# PowerSupply_12V_v1.net
KiCad netlist of a schematic drawn in EAGLE
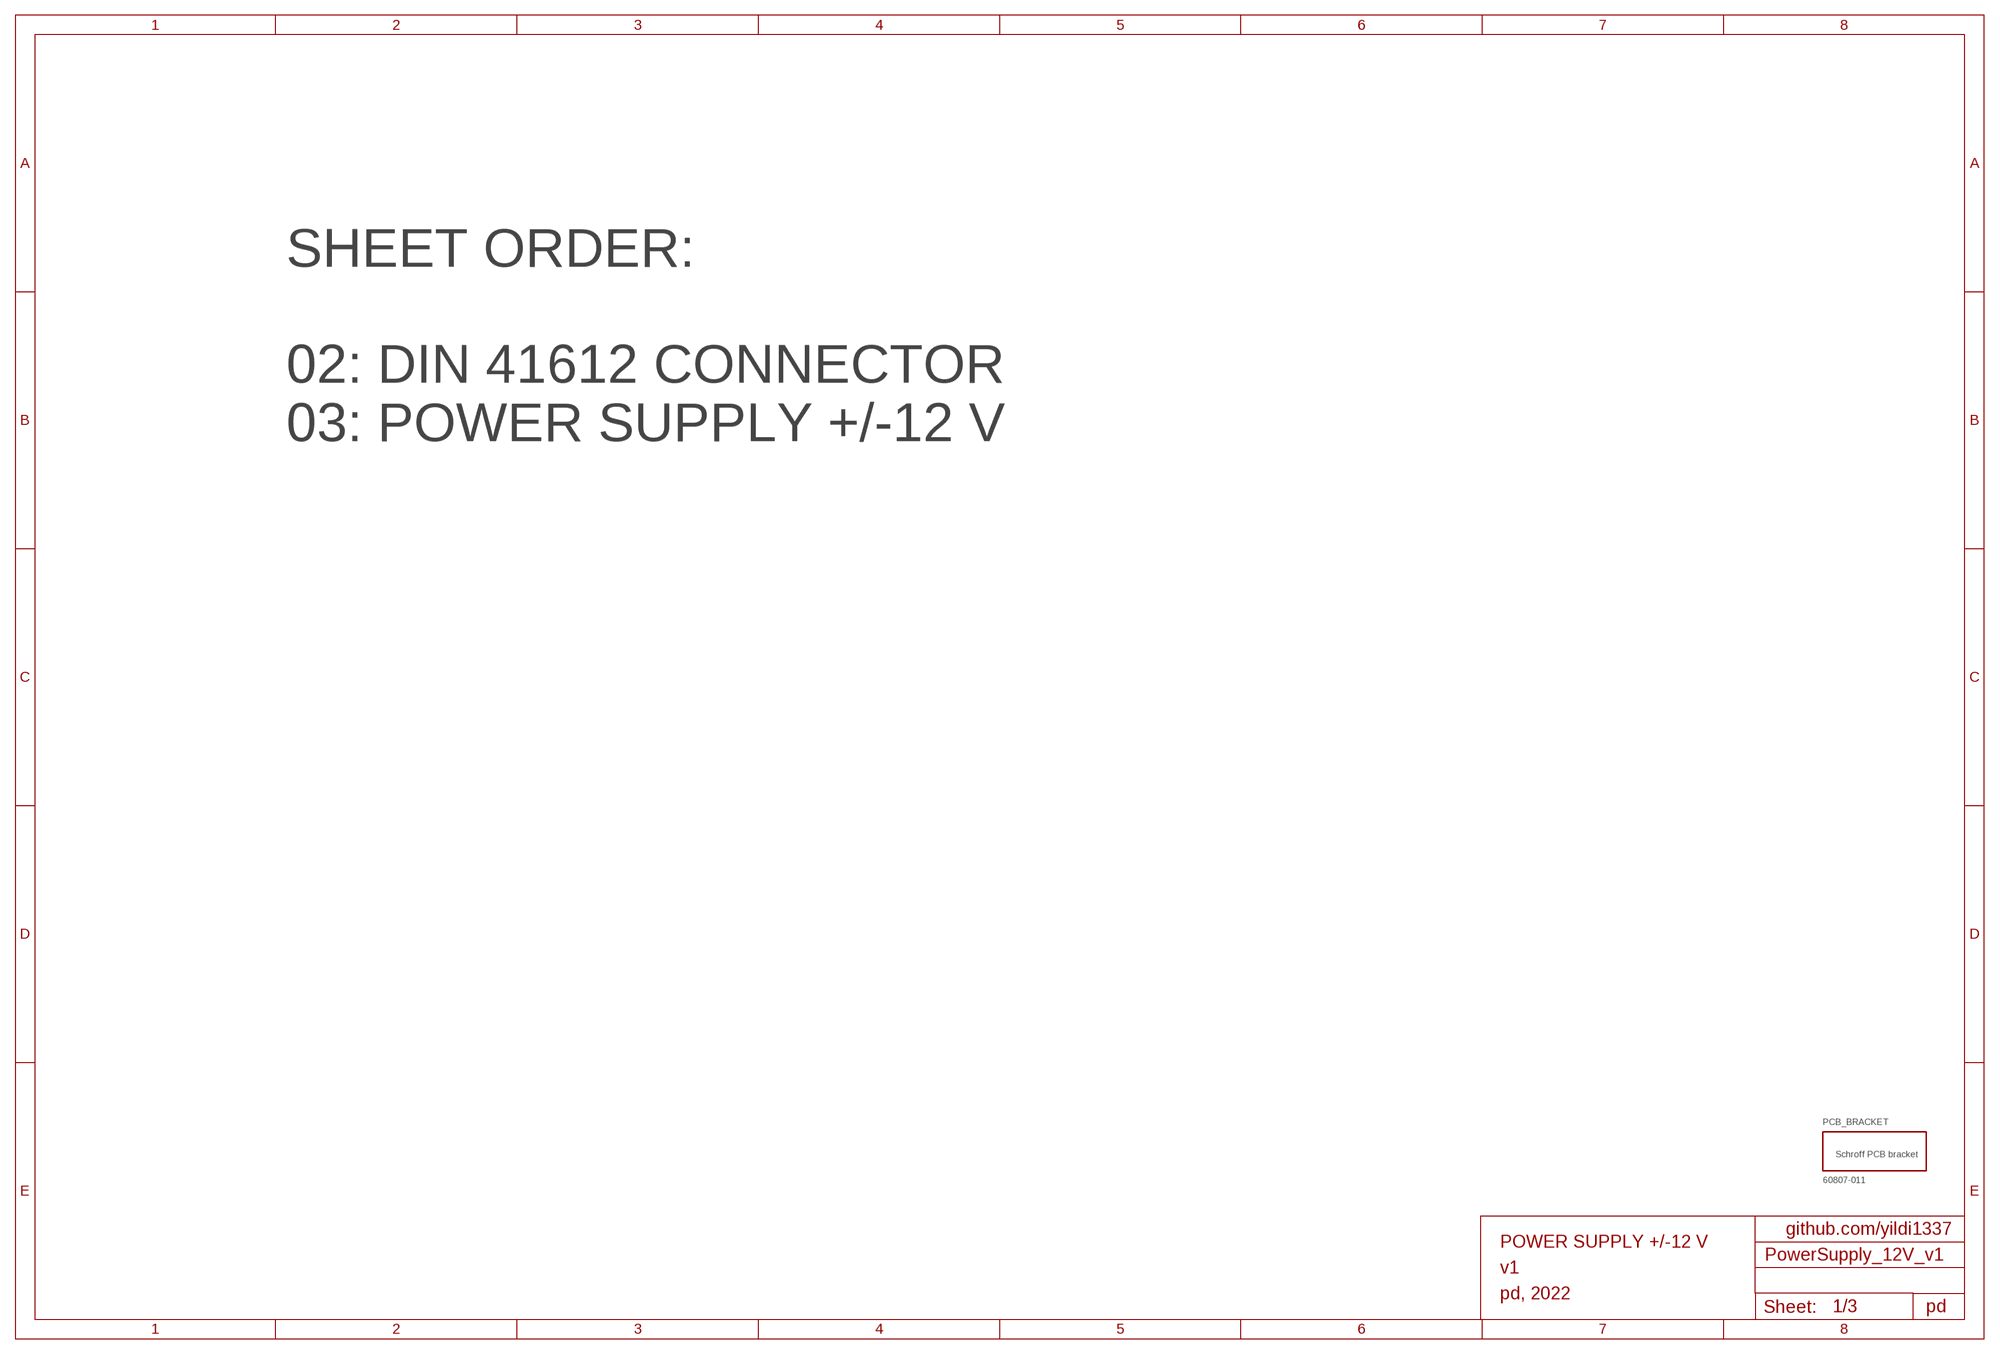
[diagram p0: schematic, sheet 1]
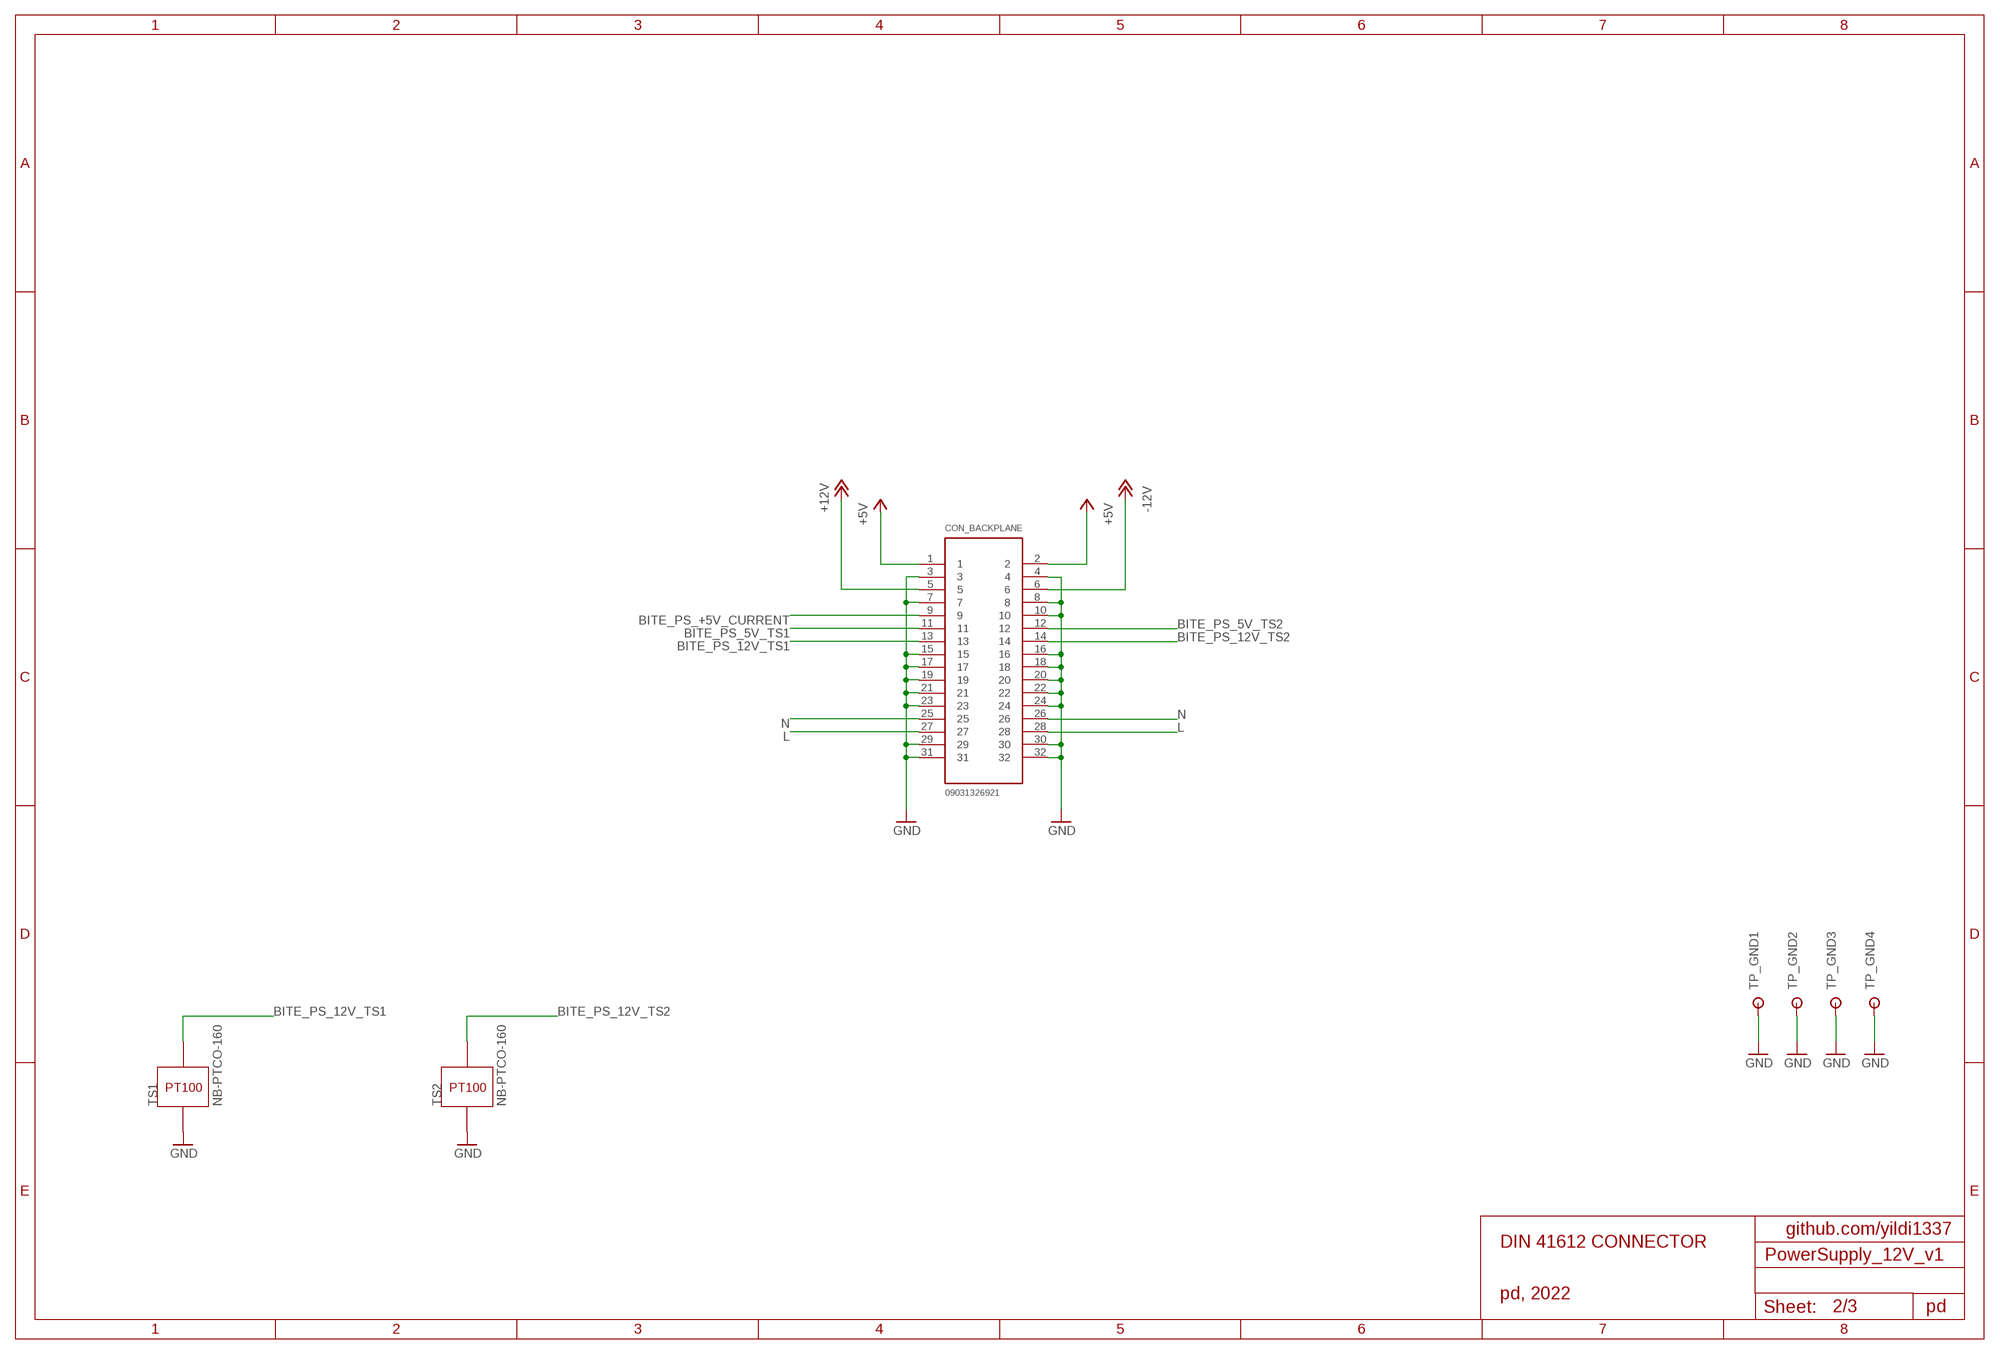
[diagram p1: schematic, sheet 2]
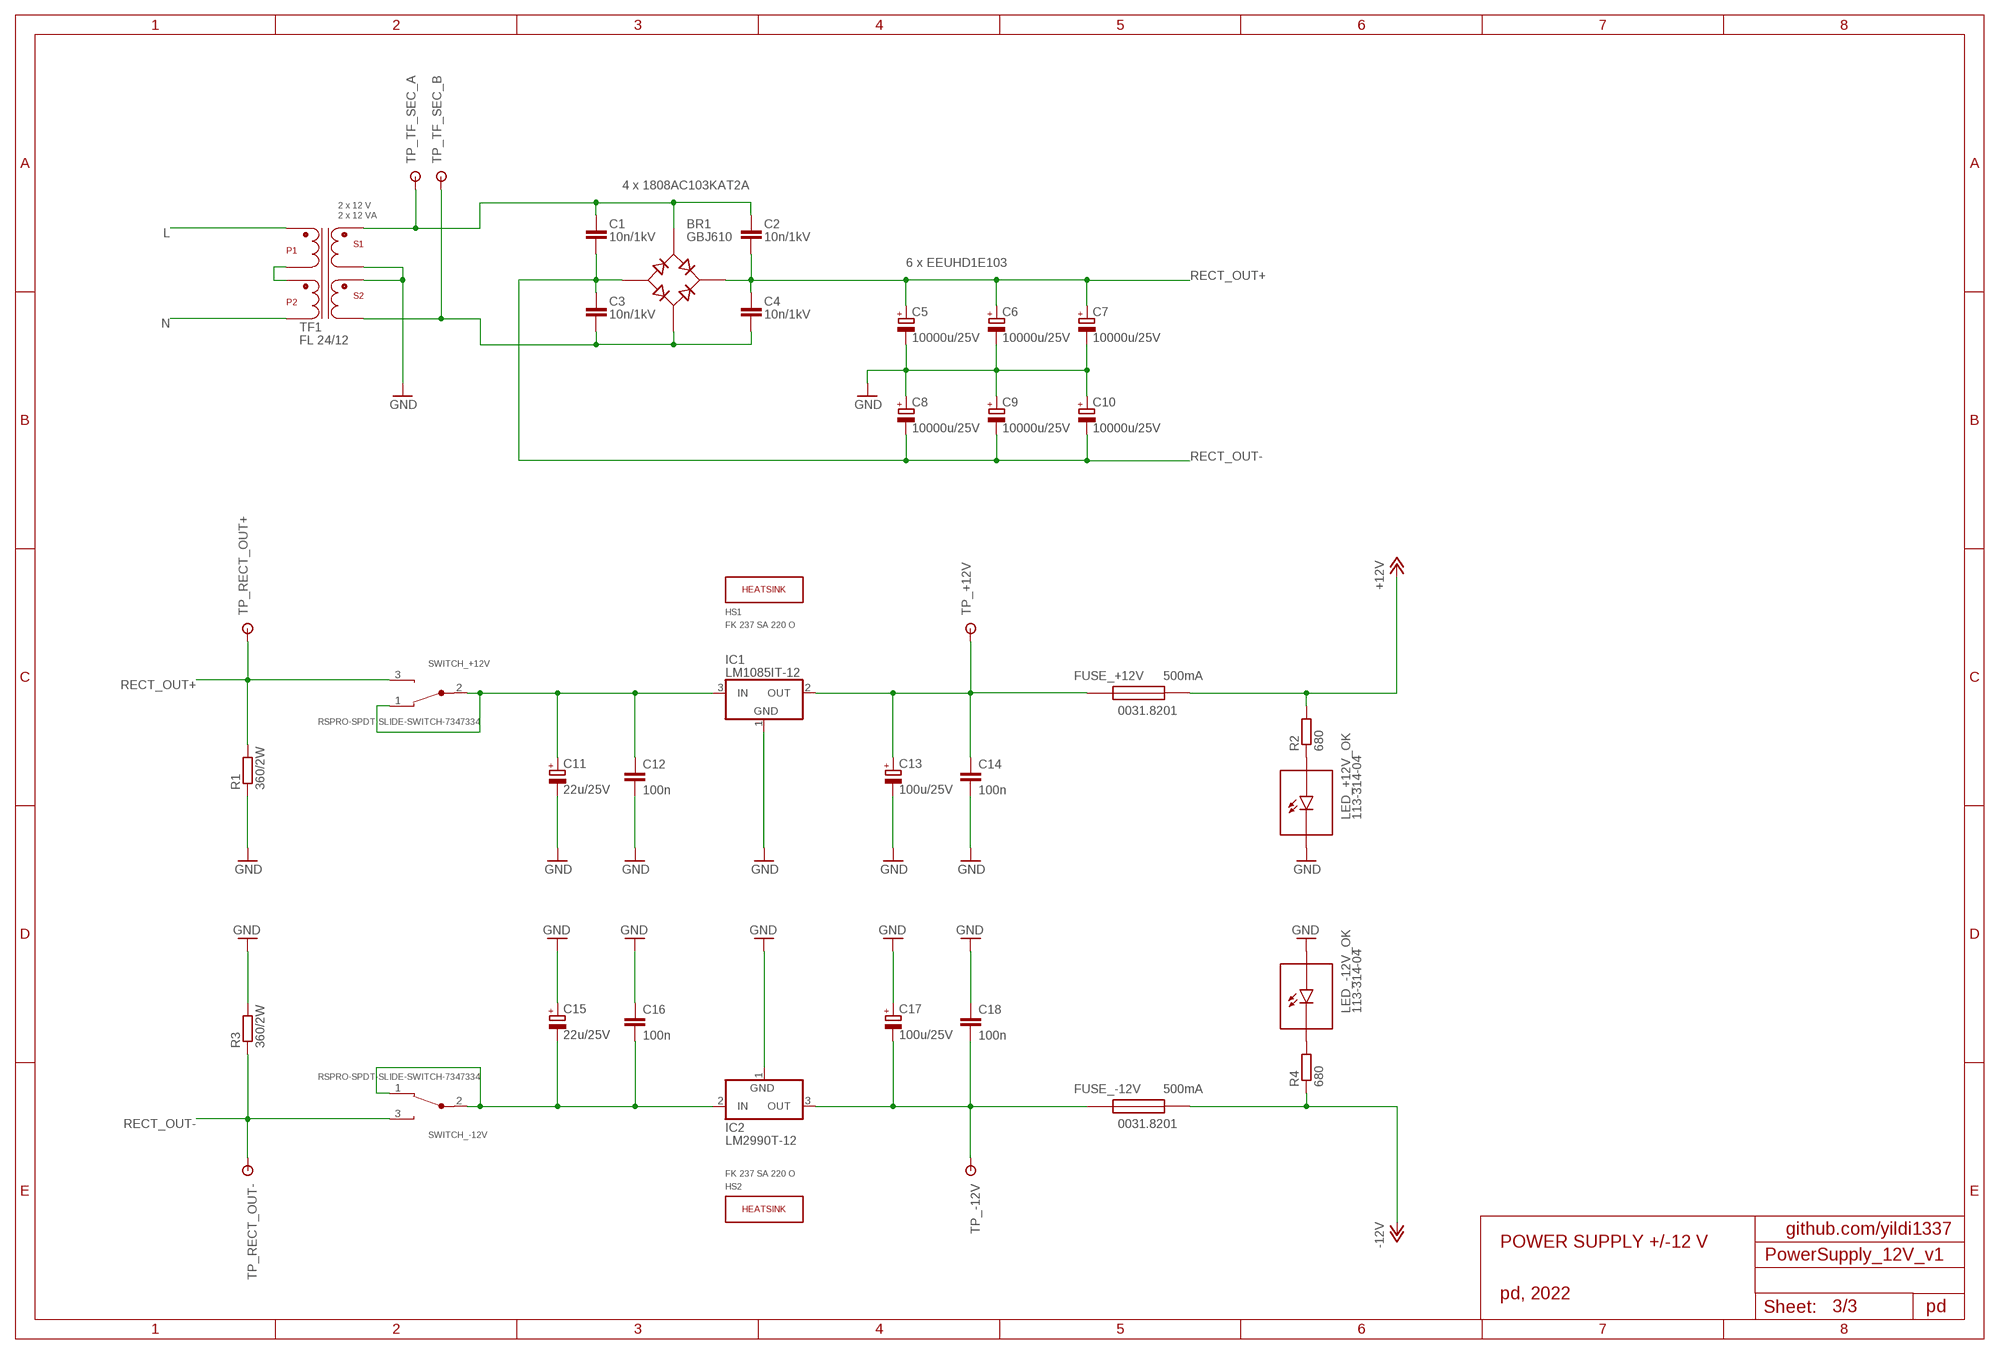
[diagram p2: schematic, sheet 3]

(export (version "E")
  (design (tool "Eeschema 10.0.6"))
  (components
    (comp (ref "BR1")
      (value "GBJ610")
      (footprint "eagle-import:GBJ610")
      (libsource (lib "eagle-import") (part "GBJ610"))
    )
    (comp (ref "C1")
      (value "10n/1kV")
      (footprint "eagle-import:C1808")
      (libsource (lib "eagle-import") (part "C-EUC1808"))
    )
    (comp (ref "C2")
      (value "10n/1kV")
      (footprint "eagle-import:C1808")
      (libsource (lib "eagle-import") (part "C-EUC1808"))
    )
    (comp (ref "C3")
      (value "10n/1kV")
      (footprint "eagle-import:C1808")
      (libsource (lib "eagle-import") (part "C-EUC1808"))
    )
    (comp (ref "C4")
      (value "10n/1kV")
      (footprint "eagle-import:C1808")
      (libsource (lib "eagle-import") (part "C-EUC1808"))
    )
    (comp (ref "C5")
      (value "10000u/25V")
      (footprint "eagle-import:EEUHD1E103")
      (libsource (lib "eagle-import") (part "EEUHD1E103"))
    )
    (comp (ref "C6")
      (value "10000u/25V")
      (footprint "eagle-import:EEUHD1E103")
      (libsource (lib "eagle-import") (part "EEUHD1E103"))
    )
    (comp (ref "C7")
      (value "10000u/25V")
      (footprint "eagle-import:EEUHD1E103")
      (libsource (lib "eagle-import") (part "EEUHD1E103"))
    )
    (comp (ref "C8")
      (value "10000u/25V")
      (footprint "eagle-import:EEUHD1E103")
      (libsource (lib "eagle-import") (part "EEUHD1E103"))
    )
    (comp (ref "C9")
      (value "10000u/25V")
      (footprint "eagle-import:EEUHD1E103")
      (libsource (lib "eagle-import") (part "EEUHD1E103"))
    )
    (comp (ref "C10")
      (value "10000u/25V")
      (footprint "eagle-import:EEUHD1E103")
      (libsource (lib "eagle-import") (part "EEUHD1E103"))
    )
    (comp (ref "C11")
      (value "22u/25V")
      (footprint "eagle-import:153CLV-0505")
      (libsource (lib "eagle-import") (part "CPOL-EU153CLV-0505"))
    )
    (comp (ref "C12")
      (value "100n")
      (footprint "eagle-import:C0603")
      (libsource (lib "eagle-import") (part "C-EUC0603"))
    )
    (comp (ref "C13")
      (value "100u/25V")
      (footprint "eagle-import:153CLV-0810")
      (libsource (lib "eagle-import") (part "CPOL-EU153CLV-0810"))
    )
    (comp (ref "C14")
      (value "100n")
      (footprint "eagle-import:C0603")
      (libsource (lib "eagle-import") (part "C-EUC0603"))
    )
    (comp (ref "C15")
      (value "22u/25V")
      (footprint "eagle-import:153CLV-0505")
      (libsource (lib "eagle-import") (part "CPOL-EU153CLV-0505"))
    )
    (comp (ref "C16")
      (value "100n")
      (footprint "eagle-import:C0603")
      (libsource (lib "eagle-import") (part "C-EUC0603"))
    )
    (comp (ref "C17")
      (value "100u/25V")
      (footprint "eagle-import:153CLV-0810")
      (libsource (lib "eagle-import") (part "CPOL-EU153CLV-0810"))
    )
    (comp (ref "C18")
      (value "100n")
      (footprint "eagle-import:C0603")
      (libsource (lib "eagle-import") (part "C-EUC0603"))
    )
    (comp (ref "FUSE_+12V")
      (value "0031.8201")
      (footprint "eagle-import:0031.8201")
      (libsource (lib "eagle-import") (part "0031.8201"))
    )
    (comp (ref "FUSE_-12V")
      (value "0031.8201")
      (footprint "eagle-import:0031.8201")
      (libsource (lib "eagle-import") (part "0031.8201"))
    )
    (comp (ref "HS1")
      (value "FK 237 SA 220 O")
      (footprint "eagle-import:FK_237_SA_220_O")
      (libsource (lib "eagle-import") (part "FK_237_SA_220_O"))
    )
    (comp (ref "HS2")
      (value "FK 237 SA 220 O")
      (footprint "eagle-import:FK_237_SA_220_O")
      (libsource (lib "eagle-import") (part "FK_237_SA_220_O"))
    )
    (comp (ref "IC1")
      (value "LM1085IT-12")
      (footprint "eagle-import:LM1085IT-12")
      (libsource (lib "eagle-import") (part "LM1085IT-12"))
    )
    (comp (ref "IC2")
      (value "LM2990T-12")
      (footprint "eagle-import:LM2990T-12")
      (libsource (lib "eagle-import") (part "LM2990T-12"))
    )
    (comp (ref "LED_+12V_OK")
      (value "113-314-04")
      (footprint "eagle-import:113-314-04")
      (libsource (lib "eagle-import") (part "113-314-04"))
    )
    (comp (ref "LED_-12V_OK")
      (value "113-314-04")
      (footprint "eagle-import:113-314-04")
      (libsource (lib "eagle-import") (part "113-314-04"))
    )
    (comp (ref "R1")
      (value "360/2W")
      (footprint "eagle-import:R2010")
      (libsource (lib "eagle-import") (part "R-EU_R2010"))
    )
    (comp (ref "R2")
      (value "680")
      (footprint "eagle-import:R0603")
      (libsource (lib "eagle-import") (part "R-EU_R0603"))
    )
    (comp (ref "R3")
      (value "360/2W")
      (footprint "eagle-import:R2010")
      (libsource (lib "eagle-import") (part "R-EU_R2010"))
    )
    (comp (ref "R4")
      (value "680")
      (footprint "eagle-import:R0603")
      (libsource (lib "eagle-import") (part "R-EU_R0603"))
    )
    (comp (ref "SWITCH_+12V")
      (value "RSPRO-SPDT-SLIDE-SWITCH-7347334")
      (footprint "eagle-import:RSPRO-SPDT-SLIDE-SWITCH-7347334")
      (libsource (lib "eagle-import") (part "RSPRO-SPDT-SLIDE-SWITCH-7347334"))
    )
    (comp (ref "SWITCH_-12V")
      (value "RSPRO-SPDT-SLIDE-SWITCH-7347334")
      (footprint "eagle-import:RSPRO-SPDT-SLIDE-SWITCH-7347334")
      (libsource (lib "eagle-import") (part "RSPRO-SPDT-SLIDE-SWITCH-7347334"))
    )
    (comp (ref "TF1")
      (value "FL 24/12")
      (footprint "eagle-import:FL_24-12")
      (libsource (lib "eagle-import") (part "FL_24-12"))
    )
    (comp (ref "TP_+12V")
      (value "RSPRO-1MM-TERMINAL-POST-2622034")
      (footprint "eagle-import:RSPRO-1MM-TERMINAL-POST-2622034")
      (libsource (lib "eagle-import") (part "RSPRO-1MM-TERMINAL-POST-2622034"))
    )
    (comp (ref "TP_-12V")
      (value "RSPRO-1MM-TERMINAL-POST-2622034")
      (footprint "eagle-import:RSPRO-1MM-TERMINAL-POST-2622034")
      (libsource (lib "eagle-import") (part "RSPRO-1MM-TERMINAL-POST-2622034"))
    )
    (comp (ref "TP_RECT_OUT+")
      (value "RSPRO-1MM-TERMINAL-POST-2622034")
      (footprint "eagle-import:RSPRO-1MM-TERMINAL-POST-2622034")
      (libsource (lib "eagle-import") (part "RSPRO-1MM-TERMINAL-POST-2622034"))
    )
    (comp (ref "TP_RECT_OUT-")
      (value "RSPRO-1MM-TERMINAL-POST-2622034")
      (footprint "eagle-import:RSPRO-1MM-TERMINAL-POST-2622034")
      (libsource (lib "eagle-import") (part "RSPRO-1MM-TERMINAL-POST-2622034"))
    )
    (comp (ref "TP_TF_SEC_A")
      (value "RSPRO-1MM-TERMINAL-POST-2622034")
      (footprint "eagle-import:RSPRO-1MM-TERMINAL-POST-2622034")
      (libsource (lib "eagle-import") (part "RSPRO-1MM-TERMINAL-POST-2622034"))
    )
    (comp (ref "TP_TF_SEC_B")
      (value "RSPRO-1MM-TERMINAL-POST-2622034")
      (footprint "eagle-import:RSPRO-1MM-TERMINAL-POST-2622034")
      (libsource (lib "eagle-import") (part "RSPRO-1MM-TERMINAL-POST-2622034"))
    )
    (comp (ref "CON_BACKPLANE")
      (value "09031326921")
      (footprint "eagle-import:09031326921")
      (libsource (lib "eagle-import") (part "09031326921"))
    )
    (comp (ref "TP_GND1")
      (value "RSPRO-1MM-TERMINAL-POST-2622034")
      (footprint "eagle-import:RSPRO-1MM-TERMINAL-POST-2622034")
      (libsource (lib "eagle-import") (part "RSPRO-1MM-TERMINAL-POST-2622034"))
    )
    (comp (ref "TP_GND2")
      (value "RSPRO-1MM-TERMINAL-POST-2622034")
      (footprint "eagle-import:RSPRO-1MM-TERMINAL-POST-2622034")
      (libsource (lib "eagle-import") (part "RSPRO-1MM-TERMINAL-POST-2622034"))
    )
    (comp (ref "TP_GND3")
      (value "RSPRO-1MM-TERMINAL-POST-2622034")
      (footprint "eagle-import:RSPRO-1MM-TERMINAL-POST-2622034")
      (libsource (lib "eagle-import") (part "RSPRO-1MM-TERMINAL-POST-2622034"))
    )
    (comp (ref "TP_GND4")
      (value "RSPRO-1MM-TERMINAL-POST-2622034")
      (footprint "eagle-import:RSPRO-1MM-TERMINAL-POST-2622034")
      (libsource (lib "eagle-import") (part "RSPRO-1MM-TERMINAL-POST-2622034"))
    )
    (comp (ref "TS1")
      (value "NB-PTCO-160")
      (footprint "eagle-import:NB-PTCO-160")
      (libsource (lib "eagle-import") (part "NB-PTCO-160"))
    )
    (comp (ref "TS2")
      (value "NB-PTCO-160")
      (footprint "eagle-import:NB-PTCO-160")
      (libsource (lib "eagle-import") (part "NB-PTCO-160"))
    )
    (comp (ref "PCB_BRACKET")
      (value "60807-011")
      (footprint "eagle-import:60807-011")
      (libsource (lib "eagle-import") (part "60807-011"))
    )
  )
  (nets
    (net (code "1") (name "+5V") (class "Default")
      (node (ref "CON_BACKPLANE") (pin "1") (pinfunction "1_1") (pintype "bidirectional"))
      (node (ref "CON_BACKPLANE") (pin "2") (pinfunction "2_2") (pintype "bidirectional"))
    )
    (net (code "2") (name "+12V") (class "Default")
      (node (ref "CON_BACKPLANE") (pin "5") (pinfunction "5_5") (pintype "bidirectional"))
      (node (ref "FUSE_+12V") (pin "2") (pinfunction "P$2_2") (pintype "bidirectional"))
      (node (ref "R2") (pin "2") (pinfunction "2_2") (pintype "passive"))
    )
    (net (code "3") (name "-12V") (class "Default")
      (node (ref "CON_BACKPLANE") (pin "6") (pinfunction "6_6") (pintype "bidirectional"))
      (node (ref "FUSE_-12V") (pin "2") (pinfunction "P$2_2") (pintype "bidirectional"))
      (node (ref "R4") (pin "1") (pinfunction "1_1") (pintype "passive"))
    )
    (net (code "4") (name "BITE_PS_+5V_CURRENT") (class "Default")
      (node (ref "CON_BACKPLANE") (pin "9") (pinfunction "9_9") (pintype "bidirectional"))
    )
    (net (code "5") (name "BITE_PS_5V_TS1") (class "Default")
      (node (ref "CON_BACKPLANE") (pin "11") (pinfunction "11_11") (pintype "bidirectional"))
    )
    (net (code "6") (name "BITE_PS_5V_TS2") (class "Default")
      (node (ref "CON_BACKPLANE") (pin "12") (pinfunction "12_12") (pintype "bidirectional"))
    )
    (net (code "7") (name "BITE_PS_12V_TS1") (class "Default")
      (node (ref "CON_BACKPLANE") (pin "13") (pinfunction "13_13") (pintype "bidirectional"))
      (node (ref "TS1") (pin "1") (pinfunction "P$1_1") (pintype "passive"))
    )
    (net (code "8") (name "BITE_PS_12V_TS2") (class "Default")
      (node (ref "CON_BACKPLANE") (pin "14") (pinfunction "14_14") (pintype "bidirectional"))
      (node (ref "TS2") (pin "1") (pinfunction "P$1_1") (pintype "passive"))
    )
    (net (code "9") (name "GND") (class "Default")
      (node (ref "C10") (pin "+") (pinfunction "+_+") (pintype "passive"))
      (node (ref "C11") (pin "-") (pinfunction "-_-") (pintype "passive"))
      (node (ref "C12") (pin "2") (pinfunction "2_2") (pintype "passive"))
      (node (ref "C13") (pin "-") (pinfunction "-_-") (pintype "passive"))
      (node (ref "C14") (pin "2") (pinfunction "2_2") (pintype "passive"))
      (node (ref "C15") (pin "+") (pinfunction "+_+") (pintype "passive"))
      (node (ref "C16") (pin "1") (pinfunction "1_1") (pintype "passive"))
      (node (ref "C17") (pin "+") (pinfunction "+_+") (pintype "passive"))
      (node (ref "C18") (pin "1") (pinfunction "1_1") (pintype "passive"))
      (node (ref "C5") (pin "-") (pinfunction "-_-") (pintype "passive"))
      (node (ref "C6") (pin "-") (pinfunction "-_-") (pintype "passive"))
      (node (ref "C7") (pin "-") (pinfunction "-_-") (pintype "passive"))
      (node (ref "C8") (pin "+") (pinfunction "+_+") (pintype "passive"))
      (node (ref "C9") (pin "+") (pinfunction "+_+") (pintype "passive"))
      (node (ref "CON_BACKPLANE") (pin "10") (pinfunction "10_10") (pintype "bidirectional"))
      (node (ref "CON_BACKPLANE") (pin "15") (pinfunction "15_15") (pintype "bidirectional"))
      (node (ref "CON_BACKPLANE") (pin "16") (pinfunction "16_16") (pintype "bidirectional"))
      (node (ref "CON_BACKPLANE") (pin "17") (pinfunction "17_17") (pintype "bidirectional"))
      (node (ref "CON_BACKPLANE") (pin "18") (pinfunction "18_18") (pintype "bidirectional"))
      (node (ref "CON_BACKPLANE") (pin "19") (pinfunction "19_19") (pintype "bidirectional"))
      (node (ref "CON_BACKPLANE") (pin "20") (pinfunction "20_20") (pintype "bidirectional"))
      (node (ref "CON_BACKPLANE") (pin "21") (pinfunction "21_21") (pintype "bidirectional"))
      (node (ref "CON_BACKPLANE") (pin "22") (pinfunction "22_22") (pintype "bidirectional"))
      (node (ref "CON_BACKPLANE") (pin "23") (pinfunction "23_23") (pintype "bidirectional"))
      (node (ref "CON_BACKPLANE") (pin "24") (pinfunction "24_24") (pintype "bidirectional"))
      (node (ref "CON_BACKPLANE") (pin "29") (pinfunction "29_29") (pintype "bidirectional"))
      (node (ref "CON_BACKPLANE") (pin "3") (pinfunction "3_3") (pintype "bidirectional"))
      (node (ref "CON_BACKPLANE") (pin "30") (pinfunction "30_30") (pintype "bidirectional"))
      (node (ref "CON_BACKPLANE") (pin "31") (pinfunction "31_31") (pintype "bidirectional"))
      (node (ref "CON_BACKPLANE") (pin "32") (pinfunction "32_32") (pintype "bidirectional"))
      (node (ref "CON_BACKPLANE") (pin "4") (pinfunction "4_4") (pintype "bidirectional"))
      (node (ref "CON_BACKPLANE") (pin "7") (pinfunction "7_7") (pintype "bidirectional"))
      (node (ref "CON_BACKPLANE") (pin "8") (pinfunction "8_8") (pintype "bidirectional"))
      (node (ref "IC1") (pin "1") (pinfunction "GND_1") (pintype "passive"))
      (node (ref "IC2") (pin "1") (pinfunction "GND_1") (pintype "passive"))
      (node (ref "LED_+12V_OK") (pin "-") (pinfunction "C_-") (pintype "passive"))
      (node (ref "LED_-12V_OK") (pin "+") (pinfunction "A_+") (pintype "passive"))
      (node (ref "R1") (pin "1") (pinfunction "1_1") (pintype "passive"))
      (node (ref "R3") (pin "2") (pinfunction "2_2") (pintype "passive"))
      (node (ref "TF1") (pin "S1B") (pinfunction "S1B_S1B") (pintype "passive"))
      (node (ref "TF1") (pin "S2A") (pinfunction "S2A_S2A") (pintype "passive"))
      (node (ref "TP_GND1") (pin "P$1") (pinfunction "P$1_P$1") (pintype "bidirectional"))
      (node (ref "TP_GND2") (pin "P$1") (pinfunction "P$1_P$1") (pintype "bidirectional"))
      (node (ref "TP_GND3") (pin "P$1") (pinfunction "P$1_P$1") (pintype "bidirectional"))
      (node (ref "TP_GND4") (pin "P$1") (pinfunction "P$1_P$1") (pintype "bidirectional"))
      (node (ref "TS1") (pin "2") (pinfunction "P$2_2") (pintype "passive"))
      (node (ref "TS2") (pin "2") (pinfunction "P$2_2") (pintype "passive"))
    )
    (net (code "10") (name "L") (class "Default")
      (node (ref "CON_BACKPLANE") (pin "27") (pinfunction "27_27") (pintype "bidirectional"))
      (node (ref "CON_BACKPLANE") (pin "28") (pinfunction "28_28") (pintype "bidirectional"))
      (node (ref "TF1") (pin "P1A") (pinfunction "P1A_P1A") (pintype "passive"))
    )
    (net (code "11") (name "N") (class "Default")
      (node (ref "CON_BACKPLANE") (pin "25") (pinfunction "25_25") (pintype "bidirectional"))
      (node (ref "CON_BACKPLANE") (pin "26") (pinfunction "26_26") (pintype "bidirectional"))
      (node (ref "TF1") (pin "P2B") (pinfunction "P2B_P2B") (pintype "passive"))
    )
    (net (code "12") (name "Net-(BR1-PadL)") (class "Default")
      (node (ref "BR1") (pin "L") (pinfunction "L_L") (pintype "bidirectional"))
      (node (ref "C1") (pin "1") (pinfunction "1_1") (pintype "passive"))
      (node (ref "C2") (pin "1") (pinfunction "1_1") (pintype "passive"))
      (node (ref "TF1") (pin "S1A") (pinfunction "S1A_S1A") (pintype "passive"))
      (node (ref "TP_TF_SEC_A") (pin "P$1") (pinfunction "P$1_P$1") (pintype "bidirectional"))
    )
    (net (code "13") (name "Net-(BR1-PadN)") (class "Default")
      (node (ref "BR1") (pin "N") (pinfunction "N_N") (pintype "bidirectional"))
      (node (ref "C3") (pin "2") (pinfunction "2_2") (pintype "passive"))
      (node (ref "C4") (pin "2") (pinfunction "2_2") (pintype "passive"))
      (node (ref "TF1") (pin "S2B") (pinfunction "S2B_S2B") (pintype "passive"))
      (node (ref "TP_TF_SEC_B") (pin "P$1") (pinfunction "P$1_P$1") (pintype "bidirectional"))
    )
    (net (code "14") (name "Net-(FUSE_+12V-P$1)") (class "Default")
      (node (ref "C13") (pin "+") (pinfunction "+_+") (pintype "passive"))
      (node (ref "C14") (pin "1") (pinfunction "1_1") (pintype "passive"))
      (node (ref "FUSE_+12V") (pin "1") (pinfunction "P$1_1") (pintype "bidirectional"))
      (node (ref "IC1") (pin "2") (pinfunction "OUT_2") (pintype "passive"))
      (node (ref "TP_+12V") (pin "P$1") (pinfunction "P$1_P$1") (pintype "bidirectional"))
    )
    (net (code "15") (name "Net-(FUSE_-12V-P$1)") (class "Default")
      (node (ref "C17") (pin "-") (pinfunction "-_-") (pintype "passive"))
      (node (ref "C18") (pin "2") (pinfunction "2_2") (pintype "passive"))
      (node (ref "FUSE_-12V") (pin "1") (pinfunction "P$1_1") (pintype "bidirectional"))
      (node (ref "IC2") (pin "3") (pinfunction "OUT_3") (pintype "passive"))
      (node (ref "TP_-12V") (pin "P$1") (pinfunction "P$1_P$1") (pintype "bidirectional"))
    )
    (net (code "16") (name "Net-(IC1-IN)") (class "Default")
      (node (ref "C11") (pin "+") (pinfunction "+_+") (pintype "passive"))
      (node (ref "C12") (pin "1") (pinfunction "1_1") (pintype "passive"))
      (node (ref "IC1") (pin "3") (pinfunction "IN_3") (pintype "input"))
      (node (ref "SWITCH_+12V") (pin "1") (pinfunction "NC_1") (pintype "passive"))
      (node (ref "SWITCH_+12V") (pin "2") (pinfunction "COM_2") (pintype "passive"))
    )
    (net (code "17") (name "Net-(IC2-IN)") (class "Default")
      (node (ref "C15") (pin "-") (pinfunction "-_-") (pintype "passive"))
      (node (ref "C16") (pin "2") (pinfunction "2_2") (pintype "passive"))
      (node (ref "IC2") (pin "2") (pinfunction "IN_2") (pintype "input"))
      (node (ref "SWITCH_-12V") (pin "1") (pinfunction "NC_1") (pintype "passive"))
      (node (ref "SWITCH_-12V") (pin "2") (pinfunction "COM_2") (pintype "passive"))
    )
    (net (code "18") (name "Net-(LED_+12V_OK-A)") (class "Default")
      (node (ref "LED_+12V_OK") (pin "+") (pinfunction "A_+") (pintype "passive"))
      (node (ref "R2") (pin "1") (pinfunction "1_1") (pintype "passive"))
    )
    (net (code "19") (name "Net-(LED_-12V_OK-C)") (class "Default")
      (node (ref "LED_-12V_OK") (pin "-") (pinfunction "C_-") (pintype "passive"))
      (node (ref "R4") (pin "2") (pinfunction "2_2") (pintype "passive"))
    )
    (net (code "20") (name "Net-(TF1-PadP1B)") (class "Default")
      (node (ref "TF1") (pin "P1B") (pinfunction "P1B_P1B") (pintype "passive"))
      (node (ref "TF1") (pin "P2A") (pinfunction "P2A_P2A") (pintype "passive"))
    )
    (net (code "21") (name "RECT_OUT+") (class "Default")
      (node (ref "BR1") (pin "+") (pinfunction "+_+") (pintype "bidirectional"))
      (node (ref "C2") (pin "2") (pinfunction "2_2") (pintype "passive"))
      (node (ref "C4") (pin "1") (pinfunction "1_1") (pintype "passive"))
      (node (ref "C5") (pin "+") (pinfunction "+_+") (pintype "passive"))
      (node (ref "C6") (pin "+") (pinfunction "+_+") (pintype "passive"))
      (node (ref "C7") (pin "+") (pinfunction "+_+") (pintype "passive"))
      (node (ref "R1") (pin "2") (pinfunction "2_2") (pintype "passive"))
      (node (ref "SWITCH_+12V") (pin "3") (pinfunction "NO_3") (pintype "passive"))
      (node (ref "TP_RECT_OUT+") (pin "P$1") (pinfunction "P$1_P$1") (pintype "bidirectional"))
    )
    (net (code "22") (name "RECT_OUT-") (class "Default")
      (node (ref "BR1") (pin "-") (pinfunction "-_-") (pintype "bidirectional"))
      (node (ref "C1") (pin "2") (pinfunction "2_2") (pintype "passive"))
      (node (ref "C10") (pin "-") (pinfunction "-_-") (pintype "passive"))
      (node (ref "C3") (pin "1") (pinfunction "1_1") (pintype "passive"))
      (node (ref "C8") (pin "-") (pinfunction "-_-") (pintype "passive"))
      (node (ref "C9") (pin "-") (pinfunction "-_-") (pintype "passive"))
      (node (ref "R3") (pin "1") (pinfunction "1_1") (pintype "passive"))
      (node (ref "SWITCH_-12V") (pin "3") (pinfunction "NO_3") (pintype "passive"))
      (node (ref "TP_RECT_OUT-") (pin "P$1") (pinfunction "P$1_P$1") (pintype "bidirectional"))
    )
  )
)
